# Mosfets.net
KiCad netlist of a schematic drawn in Altium Designer
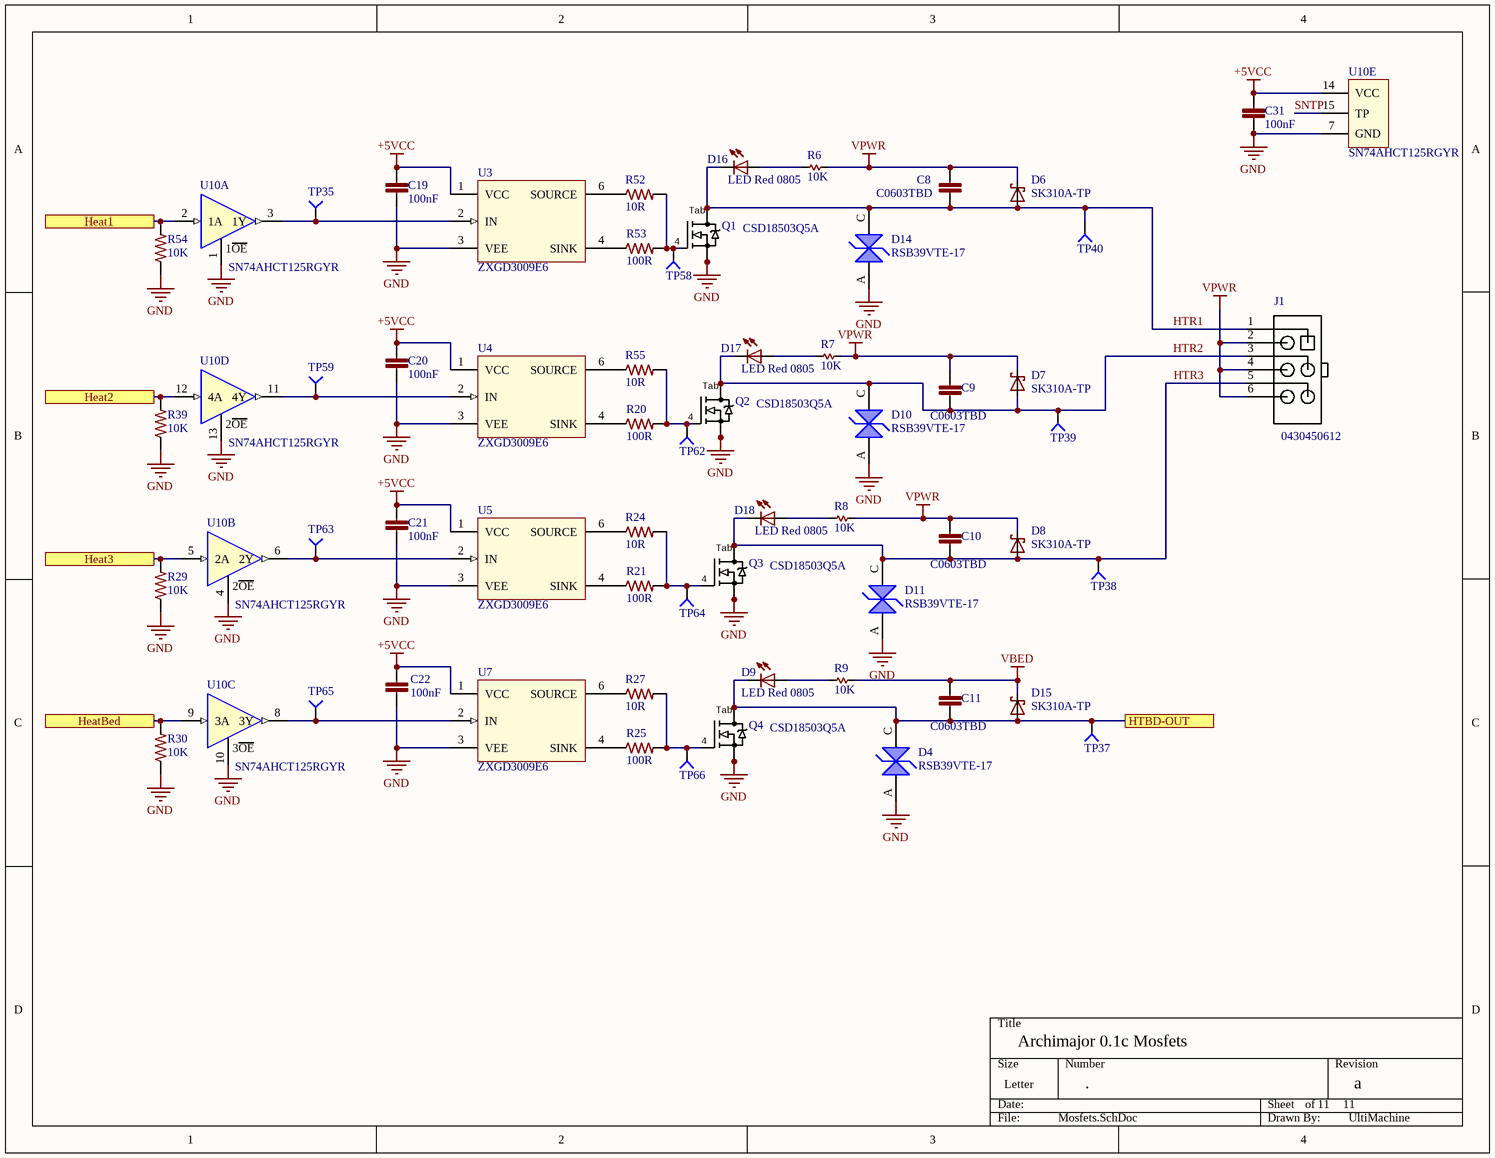
[diagram p0: Mosfets.SchDoc]

(export (version "E")
  (design (tool "Eeschema 10.0.6"))
  (components
    (comp (ref "C8")
      (value "C0603TBD")
      (footprint "C0603")
      (description "Capacitor Non Polarized")
      (libsource (lib "3Delight") (part "C0603TBD"))
    )
    (comp (ref "C9")
      (value "C0603TBD")
      (footprint "C0603")
      (description "Capacitor Non Polarized")
      (libsource (lib "3Delight") (part "C0603TBD"))
    )
    (comp (ref "C10")
      (value "C0603TBD")
      (footprint "C0603")
      (description "Capacitor Non Polarized")
      (libsource (lib "3Delight") (part "C0603TBD"))
    )
    (comp (ref "C11")
      (value "C0603TBD")
      (footprint "C0603")
      (description "Capacitor Non Polarized")
      (libsource (lib "3Delight") (part "C0603TBD"))
    )
    (comp (ref "C19")
      (value "100nF")
      (footprint "C0402")
      (description "CAP CER 0402 100nF 16V 10% X7R")
      (fields (field (name "MANUFACTURER") "Murata") (field (name "PART") "0.1uF 16V X7R 0402"))
      (libsource (lib "3Delight") (part "GRM155R71C104KA88D"))
    )
    (comp (ref "C20")
      (value "100nF")
      (footprint "C0402")
      (description "CAP CER 0402 100nF 16V 10% X7R")
      (fields (field (name "MANUFACTURER") "Murata") (field (name "PART") "0.1uF 16V X7R 0402"))
      (libsource (lib "3Delight") (part "GRM155R71C104KA88D"))
    )
    (comp (ref "C21")
      (value "100nF")
      (footprint "C0402")
      (description "CAP CER 0402 100nF 16V 10% X7R")
      (fields (field (name "MANUFACTURER") "Murata") (field (name "PART") "0.1uF 16V X7R 0402"))
      (libsource (lib "3Delight") (part "GRM155R71C104KA88D"))
    )
    (comp (ref "C22")
      (value "100nF")
      (footprint "C0402")
      (description "CAP CER 0402 100nF 16V 10% X7R")
      (fields (field (name "MANUFACTURER") "Murata") (field (name "PART") "0.1uF 16V X7R 0402"))
      (libsource (lib "") (part "GRM155R71C104KA88D_1"))
    )
    (comp (ref "C31")
      (value "100nF")
      (footprint "C0402")
      (description "CAP CER 0402 100nF 16V 10% X7R")
      (fields (field (name "MANUFACTURER") "Murata") (field (name "PART") "0.1uF 16V X7R 0402"))
      (libsource (lib "3Delight") (part "GRM155R71C104KA88D"))
    )
    (comp (ref "D4")
      (value "RSB39VTE-17")
      (footprint "SOD323-R")
      (description "DIODE TVS")
      (fields (field (name "MANUFACTURER") "Rohm") (field (name "PART") "TVS DIODE 30VWM SOD323"))
      (libsource (lib "3Delight") (part "RSB39VTE-17"))
    )
    (comp (ref "D6")
      (value "SK310A-TP")
      (footprint "SMA-SM")
      (description "DIODE Schottky 3A SMA")
      (fields (field (name "MANUFACTURER") "MCC") (field (name "PART") "Schottky Diode 100V 3A"))
      (libsource (lib "Archim_0.4") (part "SK310A"))
    )
    (comp (ref "D7")
      (value "SK310A-TP")
      (footprint "SMA-SM")
      (description "DIODE Schottky 3A SMA")
      (fields (field (name "MANUFACTURER") "MCC") (field (name "PART") "Schottky Diode 100V 3A"))
      (libsource (lib "Archim_0.4") (part "SK310A"))
    )
    (comp (ref "D8")
      (value "SK310A-TP")
      (footprint "SMA-SM")
      (description "DIODE Schottky 3A SMA")
      (fields (field (name "MANUFACTURER") "MCC") (field (name "PART") "Schottky Diode 100V 3A"))
      (libsource (lib "Archim_0.4") (part "SK310A"))
    )
    (comp (ref "D9")
      (value "Red")
      (footprint "LED2012120")
      (description "LED 0805 Red")
      (fields
        (field (name "MANUFACTURER") "Dialight")
        (field (name "PART") "LED Red 0805")
        (field (name "TOLERANCE") "-NA-")
      )
      (libsource (lib "3Delight") (part "5988110107F"))
    )
    (comp (ref "D10")
      (value "RSB39VTE-17")
      (footprint "SOD323-R")
      (description "DIODE TVS")
      (fields (field (name "MANUFACTURER") "Rohm") (field (name "PART") "TVS DIODE 30VWM SOD323"))
      (libsource (lib "3Delight") (part "RSB39VTE-17"))
    )
    (comp (ref "D11")
      (value "RSB39VTE-17")
      (footprint "SOD323-R")
      (description "DIODE TVS")
      (fields (field (name "MANUFACTURER") "Rohm") (field (name "PART") "TVS DIODE 30VWM SOD323"))
      (libsource (lib "3Delight") (part "RSB39VTE-17"))
    )
    (comp (ref "D14")
      (value "RSB39VTE-17")
      (footprint "SOD323-R")
      (description "DIODE TVS")
      (fields (field (name "MANUFACTURER") "Rohm") (field (name "PART") "TVS DIODE 30VWM SOD323"))
      (libsource (lib "3Delight") (part "RSB39VTE-17"))
    )
    (comp (ref "D15")
      (value "SK310A-TP")
      (footprint "SMA-SM")
      (description "DIODE Schottky 3A SMA")
      (fields (field (name "MANUFACTURER") "MCC") (field (name "PART") "Schottky Diode 100V 3A"))
      (libsource (lib "Archim_0.4") (part "SK310A"))
    )
    (comp (ref "D16")
      (value "Red")
      (footprint "LED2012120")
      (description "LED 0805 Red")
      (fields
        (field (name "MANUFACTURER") "Dialight")
        (field (name "PART") "LED Red 0805")
        (field (name "TOLERANCE") "-NA-")
      )
      (libsource (lib "3Delight") (part "5988110107F"))
    )
    (comp (ref "D17")
      (value "Red")
      (footprint "LED2012120")
      (description "LED 0805 Red")
      (fields
        (field (name "MANUFACTURER") "Dialight")
        (field (name "PART") "LED Red 0805")
        (field (name "TOLERANCE") "-NA-")
      )
      (libsource (lib "3Delight") (part "5988110107F"))
    )
    (comp (ref "D18")
      (value "Red")
      (footprint "LED2012120")
      (description "LED 0805 Red")
      (fields
        (field (name "MANUFACTURER") "Dialight")
        (field (name "PART") "LED Red 0805")
        (field (name "TOLERANCE") "-NA-")
      )
      (libsource (lib "3Delight") (part "5988110107F"))
    )
    (comp (ref "J1")
      (value "0430450612")
      (footprint "43045-0612")
      (description "Conn - 3mm Pitch Fixed")
      (fields (field (name "MANUFACTURER") "Molex"))
      (libsource (lib "Connectors") (part "Micro-Fit THT 6pos 3mm"))
    )
    (comp (ref "Q1")
      (value "CSD18503Q5A")
      (footprint "SOT669_Universal")
      (description "MOSFET N-CH 40V 100A 8VSON")
      (fields (field (name "MANUFACTURER") "TI"))
      (libsource (lib "Transistors") (part "CSD18503Q5A"))
    )
    (comp (ref "Q2")
      (value "CSD18503Q5A")
      (footprint "SOT669_Universal")
      (description "MOSFET N-CH 40V 100A 8VSON")
      (fields (field (name "MANUFACTURER") "TI"))
      (libsource (lib "Transistors") (part "CSD18503Q5A"))
    )
    (comp (ref "Q3")
      (value "CSD18503Q5A")
      (footprint "SOT669_Universal")
      (description "MOSFET N-CH 40V 100A 8VSON")
      (fields (field (name "MANUFACTURER") "TI"))
      (libsource (lib "Transistors") (part "CSD18503Q5A"))
    )
    (comp (ref "Q4")
      (value "CSD18503Q5A")
      (footprint "SOT669_Universal")
      (description "MOSFET N-CH 40V 100A 8VSON")
      (fields (field (name "MANUFACTURER") "TI"))
      (libsource (lib "Transistors") (part "CSD18503Q5A"))
    )
    (comp (ref "R6")
      (value "10K")
      (footprint "R0402")
      (description "RES SMD 10K OHM 1% 1/16W 0402")
      (fields (field (name "MANUFACTURER") "Yageo") (field (name "PART") "10k 1% 0402"))
      (libsource (lib "Resistors") (part "10k 1% 0402"))
    )
    (comp (ref "R7")
      (value "10K")
      (footprint "R0402")
      (description "RES SMD 10K OHM 1% 1/16W 0402")
      (fields (field (name "MANUFACTURER") "Yageo") (field (name "PART") "10k 1% 0402"))
      (libsource (lib "Resistors") (part "10k 1% 0402"))
    )
    (comp (ref "R8")
      (value "10K")
      (footprint "R0402")
      (description "RES SMD 10K OHM 1% 1/16W 0402")
      (fields (field (name "MANUFACTURER") "Yageo") (field (name "PART") "10k 1% 0402"))
      (libsource (lib "Resistors") (part "10k 1% 0402"))
    )
    (comp (ref "R9")
      (value "10K")
      (footprint "R0402")
      (description "RES SMD 10K OHM 1% 1/16W 0402")
      (fields (field (name "MANUFACTURER") "Yageo") (field (name "PART") "10k 1% 0402"))
      (libsource (lib "Resistors") (part "10k 1% 0402"))
    )
    (comp (ref "R20")
      (value "100R")
      (footprint "R0402")
      (description "RES SMD 100 OHM 1% 1/16W 0402")
      (fields (field (name "MANUFACTURER") "Yageo") (field (name "PART") "100R 1% 0402"))
      (libsource (lib "Archim") (part "RES 100R 0402 1%"))
    )
    (comp (ref "R21")
      (value "100R")
      (footprint "R0402")
      (description "RES SMD 100 OHM 1% 1/16W 0402")
      (fields (field (name "MANUFACTURER") "Yageo") (field (name "PART") "100R 1% 0402"))
      (libsource (lib "Archim") (part "RES 100R 0402 1%"))
    )
    (comp (ref "R24")
      (value "10R")
      (footprint "R0402")
      (description "RES SMD 10 OHM 1% 1/16W 0402")
      (fields (field (name "MANUFACTURER") "Yageo") (field (name "TOLERANCE") "1%"))
      (libsource (lib "3Delight") (part "RC0402FR-0710RL"))
    )
    (comp (ref "R25")
      (value "100R")
      (footprint "R0402")
      (description "RES SMD 100 OHM 1% 1/16W 0402")
      (fields (field (name "MANUFACTURER") "Yageo") (field (name "PART") "100R 1% 0402"))
      (libsource (lib "Archim") (part "RES 100R 0402 1%"))
    )
    (comp (ref "R27")
      (value "10R")
      (footprint "R0402")
      (description "RES SMD 10 OHM 1% 1/16W 0402")
      (fields (field (name "MANUFACTURER") "Yageo") (field (name "TOLERANCE") "1%"))
      (libsource (lib "3Delight") (part "RC0402FR-0710RL"))
    )
    (comp (ref "R29")
      (value "10K")
      (footprint "R0402")
      (description "RES SMD 10K OHM 1% 1/16W 0402")
      (fields (field (name "MANUFACTURER") "Yageo") (field (name "PART") "10k 1% 0402"))
      (libsource (lib "3Delight") (part "RC0402FR-0710KP"))
    )
    (comp (ref "R30")
      (value "10K")
      (footprint "R0402")
      (description "RES SMD 10K OHM 1% 1/16W 0402")
      (fields (field (name "MANUFACTURER") "Yageo") (field (name "PART") "10k 1% 0402"))
      (libsource (lib "3Delight") (part "RC0402FR-0710KP"))
    )
    (comp (ref "R39")
      (value "10K")
      (footprint "R0402")
      (description "RES SMD 10K OHM 1% 1/16W 0402")
      (fields (field (name "MANUFACTURER") "Yageo") (field (name "PART") "10k 1% 0402"))
      (libsource (lib "3Delight") (part "RC0402FR-0710KP"))
    )
    (comp (ref "R52")
      (value "10R")
      (footprint "R0402")
      (description "RES SMD 10 OHM 1% 1/16W 0402")
      (fields (field (name "MANUFACTURER") "Yageo") (field (name "TOLERANCE") "1%"))
      (libsource (lib "3Delight") (part "RC0402FR-0710RL"))
    )
    (comp (ref "R53")
      (value "100R")
      (footprint "R0402")
      (description "RES SMD 100 OHM 1% 1/16W 0402")
      (fields (field (name "MANUFACTURER") "Yageo") (field (name "PART") "100R 1% 0402"))
      (libsource (lib "Archim") (part "RES 100R 0402 1%"))
    )
    (comp (ref "R54")
      (value "10K")
      (footprint "R0402")
      (description "RES SMD 10K OHM 1% 1/16W 0402")
      (fields (field (name "MANUFACTURER") "Yageo") (field (name "PART") "10k 1% 0402"))
      (libsource (lib "3Delight") (part "RC0402FR-0710KP"))
    )
    (comp (ref "R55")
      (value "10R")
      (footprint "R0402")
      (description "RES SMD 10 OHM 1% 1/16W 0402")
      (fields (field (name "MANUFACTURER") "Yageo") (field (name "TOLERANCE") "1%"))
      (libsource (lib "3Delight") (part "RC0402FR-0710RL"))
    )
    (comp (ref "TP35")
      (value "TP4")
      (footprint "TP-2")
      (description "Socket")
      (libsource (lib "Archim") (part "Socket"))
    )
    (comp (ref "TP37")
      (value "TP4")
      (footprint "TP-2")
      (description "Socket")
      (libsource (lib "Archim") (part "Socket"))
    )
    (comp (ref "TP38")
      (value "TP4")
      (footprint "TP-2")
      (description "Socket")
      (libsource (lib "Archim") (part "Socket"))
    )
    (comp (ref "TP39")
      (value "TP4")
      (footprint "TP-2")
      (description "Socket")
      (libsource (lib "Archim") (part "Socket"))
    )
    (comp (ref "TP40")
      (value "TP4")
      (footprint "TP-2")
      (description "Socket")
      (libsource (lib "Archim") (part "Socket"))
    )
    (comp (ref "TP58")
      (value "TP4")
      (footprint "TP-2")
      (description "Socket")
      (libsource (lib "Archim") (part "Socket"))
    )
    (comp (ref "TP59")
      (value "TP4")
      (footprint "TP-2")
      (description "Socket")
      (libsource (lib "Archim") (part "Socket"))
    )
    (comp (ref "TP62")
      (value "TP4")
      (footprint "TP-2")
      (description "Socket")
      (libsource (lib "Archim") (part "Socket"))
    )
    (comp (ref "TP63")
      (value "TP4")
      (footprint "TP-2")
      (description "Socket")
      (libsource (lib "Archim") (part "Socket"))
    )
    (comp (ref "TP64")
      (value "TP4")
      (footprint "TP-2")
      (description "Socket")
      (libsource (lib "Archim") (part "Socket"))
    )
    (comp (ref "TP65")
      (value "TP4")
      (footprint "TP-2")
      (description "Socket")
      (libsource (lib "Archim") (part "Socket"))
    )
    (comp (ref "TP66")
      (value "TP4")
      (footprint "TP-2")
      (description "Socket")
      (libsource (lib "Archim") (part "Socket"))
    )
    (comp (ref "U3")
      (value "ZXGD3009E6")
      (footprint "SOT26P285X140-6L")
      (description "MOSFET DRVR 3A 1-OUT High Speed Non-Inv6-Pin SOT-26 T/R")
      (fields
        (field (name "MANUFACTURER") "Diodes Incorporated")
        (field (name "PART") "IC GATE DRVR IGBT/MOSFET SOT23-6")
      )
      (libsource (lib "3Delight") (part "ZXGD3009E6"))
    )
    (comp (ref "U4")
      (value "ZXGD3009E6")
      (footprint "SOT26P285X140-6L")
      (description "MOSFET DRVR 3A 1-OUT High Speed Non-Inv6-Pin SOT-26 T/R")
      (fields
        (field (name "MANUFACTURER") "Diodes Incorporated")
        (field (name "PART") "IC GATE DRVR IGBT/MOSFET SOT23-6")
      )
      (libsource (lib "3Delight") (part "ZXGD3009E6"))
    )
    (comp (ref "U5")
      (value "ZXGD3009E6")
      (footprint "SOT26P285X140-6L")
      (description "MOSFET DRVR 3A 1-OUT High Speed Non-Inv6-Pin SOT-26 T/R")
      (fields
        (field (name "MANUFACTURER") "Diodes Incorporated")
        (field (name "PART") "IC GATE DRVR IGBT/MOSFET SOT23-6")
      )
      (libsource (lib "3Delight") (part "ZXGD3009E6"))
    )
    (comp (ref "U7")
      (value "ZXGD3009E6")
      (footprint "SOT26P285X140-6L")
      (description "MOSFET DRVR 3A 1-OUT High Speed Non-Inv6-Pin SOT-26 T/R")
      (fields
        (field (name "MANUFACTURER") "Diodes Incorporated")
        (field (name "PART") "IC GATE DRVR IGBT/MOSFET SOT23-6")
      )
      (libsource (lib "3Delight") (part "ZXGD3009E6"))
    )
    (comp (ref "U10")
      (value "SN74AHCT125RGYR")
      (footprint "QFN50P350X350X100_RGY_S-PVQFN-N14")
      (description "Quadruple Bus Buffer Gates With 3-State Outputs 14-VQFN -40 to 125")
      (fields
        (field (name "MANUFACTURER") "Texas Instruments")
        (field (name "PART") "IC BUS BUFFER TRI-ST QD 14VQFN")
      )
      (libsource (lib "3Delight") (part "SN74AHCT125"))
    )
  )
  (nets
    (net (code "1") (name "+5VCC") (class "Default")
      (node (ref "C19") (pin "2") (pinfunction "2_2") (pintype "passive"))
      (node (ref "C20") (pin "2") (pinfunction "2_2") (pintype "passive"))
      (node (ref "C21") (pin "2") (pinfunction "2_2") (pintype "passive"))
      (node (ref "C22") (pin "1") (pinfunction "1_1") (pintype "passive"))
      (node (ref "C31") (pin "2") (pinfunction "2_2") (pintype "passive"))
      (node (ref "U10") (pin "14") (pinfunction "VCC_14") (pintype "power_in"))
      (node (ref "U3") (pin "1") (pinfunction "VCC_1") (pintype "power_in"))
      (node (ref "U4") (pin "1") (pinfunction "VCC_1") (pintype "power_in"))
      (node (ref "U5") (pin "1") (pinfunction "VCC_1") (pintype "power_in"))
      (node (ref "U7") (pin "1") (pinfunction "VCC_1") (pintype "power_in"))
    )
    (net (code "2") (name "/HTBD-OUT") (class "Default")
      (node (ref "C11") (pin "2") (pinfunction "2_2") (pintype "passive"))
      (node (ref "D15") (pin "A") (pinfunction "A_A") (pintype "passive"))
      (node (ref "D4") (pin "C") (pinfunction "C_C") (pintype "power_in"))
      (node (ref "D9") (pin "C") (pinfunction "C_C") (pintype "passive"))
      (node (ref "Q4") (pin "TAB") (pinfunction "D_TAB") (pintype "passive"))
      (node (ref "TP37") (pin "1") (pinfunction "1_1") (pintype "passive"))
    )
    (net (code "3") (name "/HTR1") (class "Default")
      (node (ref "C8") (pin "2") (pinfunction "2_2") (pintype "passive"))
      (node (ref "D14") (pin "C") (pinfunction "C_C") (pintype "power_in"))
      (node (ref "D16") (pin "C") (pinfunction "C_C") (pintype "passive"))
      (node (ref "D6") (pin "A") (pinfunction "A_A") (pintype "passive"))
      (node (ref "J1") (pin "1") (pinfunction "1_1") (pintype "power_in"))
      (node (ref "Q1") (pin "TAB") (pinfunction "D_TAB") (pintype "passive"))
      (node (ref "TP40") (pin "1") (pinfunction "1_1") (pintype "passive"))
    )
    (net (code "4") (name "/HTR2") (class "Default")
      (node (ref "C9") (pin "2") (pinfunction "2_2") (pintype "passive"))
      (node (ref "D10") (pin "C") (pinfunction "C_C") (pintype "power_in"))
      (node (ref "D17") (pin "C") (pinfunction "C_C") (pintype "passive"))
      (node (ref "D7") (pin "A") (pinfunction "A_A") (pintype "passive"))
      (node (ref "J1") (pin "3") (pinfunction "3_3") (pintype "power_in"))
      (node (ref "Q2") (pin "TAB") (pinfunction "D_TAB") (pintype "passive"))
      (node (ref "TP39") (pin "1") (pinfunction "1_1") (pintype "passive"))
    )
    (net (code "5") (name "/HTR3") (class "Default")
      (node (ref "C10") (pin "2") (pinfunction "2_2") (pintype "passive"))
      (node (ref "D11") (pin "C") (pinfunction "C_C") (pintype "power_in"))
      (node (ref "D18") (pin "C") (pinfunction "C_C") (pintype "passive"))
      (node (ref "D8") (pin "A") (pinfunction "A_A") (pintype "passive"))
      (node (ref "J1") (pin "5") (pinfunction "5_5") (pintype "power_in"))
      (node (ref "Q3") (pin "TAB") (pinfunction "D_TAB") (pintype "passive"))
      (node (ref "TP38") (pin "1") (pinfunction "1_1") (pintype "passive"))
    )
    (net (code "6") (name "/Heat1") (class "Default")
      (node (ref "R54") (pin "2") (pinfunction "2_2") (pintype "passive"))
      (node (ref "U10") (pin "2") (pinfunction "1A_2") (pintype "input"))
    )
    (net (code "7") (name "/Heat2") (class "Default")
      (node (ref "R39") (pin "2") (pinfunction "2_2") (pintype "passive"))
      (node (ref "U10") (pin "12") (pinfunction "4A_12") (pintype "input"))
    )
    (net (code "8") (name "/Heat3") (class "Default")
      (node (ref "R29") (pin "2") (pinfunction "2_2") (pintype "passive"))
      (node (ref "U10") (pin "5") (pinfunction "2A_5") (pintype "input"))
    )
    (net (code "9") (name "/HeatBed") (class "Default")
      (node (ref "R30") (pin "2") (pinfunction "2_2") (pintype "passive"))
      (node (ref "U10") (pin "9") (pinfunction "3A_9") (pintype "input"))
    )
    (net (code "10") (name "/SNTP") (class "Default")
      (node (ref "U10") (pin "15") (pinfunction "TP_15") (pintype "power_in"))
    )
    (net (code "11") (name "GND") (class "Default")
      (node (ref "C19") (pin "1") (pinfunction "1_1") (pintype "passive"))
      (node (ref "C20") (pin "1") (pinfunction "1_1") (pintype "passive"))
      (node (ref "C21") (pin "1") (pinfunction "1_1") (pintype "passive"))
      (node (ref "C22") (pin "2") (pinfunction "2_2") (pintype "passive"))
      (node (ref "C31") (pin "1") (pinfunction "1_1") (pintype "passive"))
      (node (ref "D10") (pin "A") (pinfunction "A_A") (pintype "power_in"))
      (node (ref "D11") (pin "A") (pinfunction "A_A") (pintype "power_in"))
      (node (ref "D14") (pin "A") (pinfunction "A_A") (pintype "power_in"))
      (node (ref "D4") (pin "A") (pinfunction "A_A") (pintype "power_in"))
      (node (ref "Q1") (pin "1") (pinfunction "S_1") (pintype "passive"))
      (node (ref "Q1") (pin "2") (pinfunction "S_2") (pintype "passive"))
      (node (ref "Q1") (pin "3") (pinfunction "S_3") (pintype "passive"))
      (node (ref "Q2") (pin "1") (pinfunction "S_1") (pintype "passive"))
      (node (ref "Q2") (pin "2") (pinfunction "S_2") (pintype "passive"))
      (node (ref "Q2") (pin "3") (pinfunction "S_3") (pintype "passive"))
      (node (ref "Q3") (pin "1") (pinfunction "S_1") (pintype "passive"))
      (node (ref "Q3") (pin "2") (pinfunction "S_2") (pintype "passive"))
      (node (ref "Q3") (pin "3") (pinfunction "S_3") (pintype "passive"))
      (node (ref "Q4") (pin "1") (pinfunction "S_1") (pintype "passive"))
      (node (ref "Q4") (pin "2") (pinfunction "S_2") (pintype "passive"))
      (node (ref "Q4") (pin "3") (pinfunction "S_3") (pintype "passive"))
      (node (ref "R29") (pin "1") (pinfunction "1_1") (pintype "passive"))
      (node (ref "R30") (pin "1") (pinfunction "1_1") (pintype "passive"))
      (node (ref "R39") (pin "1") (pinfunction "1_1") (pintype "passive"))
      (node (ref "R54") (pin "1") (pinfunction "1_1") (pintype "passive"))
      (node (ref "U10") (pin "1") (pinfunction "1OE_1") (pintype "power_in"))
      (node (ref "U10") (pin "10") (pinfunction "3OE_10") (pintype "power_in"))
      (node (ref "U10") (pin "13") (pinfunction "4OE_13") (pintype "power_in"))
      (node (ref "U10") (pin "4") (pinfunction "2OE_4") (pintype "power_in"))
      (node (ref "U10") (pin "7") (pinfunction "GND_7") (pintype "power_in"))
      (node (ref "U3") (pin "3") (pinfunction "VEE_3") (pintype "power_in"))
      (node (ref "U4") (pin "3") (pinfunction "VEE_3") (pintype "power_in"))
      (node (ref "U5") (pin "3") (pinfunction "VEE_3") (pintype "power_in"))
      (node (ref "U7") (pin "3") (pinfunction "VEE_3") (pintype "power_in"))
    )
    (net (code "12") (name "Net-(D9-PadA)") (class "Default")
      (node (ref "D9") (pin "A") (pinfunction "A_A") (pintype "passive"))
      (node (ref "R9") (pin "1") (pinfunction "1_1") (pintype "passive"))
    )
    (net (code "13") (name "Net-(D16-PadA)") (class "Default")
      (node (ref "D16") (pin "A") (pinfunction "A_A") (pintype "passive"))
      (node (ref "R6") (pin "1") (pinfunction "1_1") (pintype "passive"))
    )
    (net (code "14") (name "Net-(D17-PadA)") (class "Default")
      (node (ref "D17") (pin "A") (pinfunction "A_A") (pintype "passive"))
      (node (ref "R7") (pin "1") (pinfunction "1_1") (pintype "passive"))
    )
    (net (code "15") (name "Net-(D18-PadA)") (class "Default")
      (node (ref "D18") (pin "A") (pinfunction "A_A") (pintype "passive"))
      (node (ref "R8") (pin "1") (pinfunction "1_1") (pintype "passive"))
    )
    (net (code "16") (name "Net-(Q1-G)") (class "Default")
      (node (ref "Q1") (pin "4") (pinfunction "G_4") (pintype "passive"))
      (node (ref "R52") (pin "2") (pinfunction "2_2") (pintype "passive"))
      (node (ref "R53") (pin "2") (pinfunction "2_2") (pintype "passive"))
      (node (ref "TP58") (pin "1") (pinfunction "1_1") (pintype "passive"))
    )
    (net (code "17") (name "Net-(Q2-G)") (class "Default")
      (node (ref "Q2") (pin "4") (pinfunction "G_4") (pintype "passive"))
      (node (ref "R20") (pin "2") (pinfunction "2_2") (pintype "passive"))
      (node (ref "R55") (pin "2") (pinfunction "2_2") (pintype "passive"))
      (node (ref "TP62") (pin "1") (pinfunction "1_1") (pintype "passive"))
    )
    (net (code "18") (name "Net-(Q3-G)") (class "Default")
      (node (ref "Q3") (pin "4") (pinfunction "G_4") (pintype "passive"))
      (node (ref "R21") (pin "2") (pinfunction "2_2") (pintype "passive"))
      (node (ref "R24") (pin "2") (pinfunction "2_2") (pintype "passive"))
      (node (ref "TP64") (pin "1") (pinfunction "1_1") (pintype "passive"))
    )
    (net (code "19") (name "Net-(Q4-G)") (class "Default")
      (node (ref "Q4") (pin "4") (pinfunction "G_4") (pintype "passive"))
      (node (ref "R25") (pin "2") (pinfunction "2_2") (pintype "passive"))
      (node (ref "R27") (pin "2") (pinfunction "2_2") (pintype "passive"))
      (node (ref "TP66") (pin "1") (pinfunction "1_1") (pintype "passive"))
    )
    (net (code "20") (name "Net-(U3-SINK)") (class "Default")
      (node (ref "R53") (pin "1") (pinfunction "1_1") (pintype "passive"))
      (node (ref "U3") (pin "4") (pinfunction "SINK_4") (pintype "power_in"))
    )
    (net (code "21") (name "Net-(U3-SOURCE)") (class "Default")
      (node (ref "R52") (pin "1") (pinfunction "1_1") (pintype "passive"))
      (node (ref "U3") (pin "6") (pinfunction "SOURCE_6") (pintype "power_in"))
    )
    (net (code "22") (name "Net-(U4-SINK)") (class "Default")
      (node (ref "R20") (pin "1") (pinfunction "1_1") (pintype "passive"))
      (node (ref "U4") (pin "4") (pinfunction "SINK_4") (pintype "power_in"))
    )
    (net (code "23") (name "Net-(U4-SOURCE)") (class "Default")
      (node (ref "R55") (pin "1") (pinfunction "1_1") (pintype "passive"))
      (node (ref "U4") (pin "6") (pinfunction "SOURCE_6") (pintype "power_in"))
    )
    (net (code "24") (name "Net-(U5-SINK)") (class "Default")
      (node (ref "R21") (pin "1") (pinfunction "1_1") (pintype "passive"))
      (node (ref "U5") (pin "4") (pinfunction "SINK_4") (pintype "power_in"))
    )
    (net (code "25") (name "Net-(U5-SOURCE)") (class "Default")
      (node (ref "R24") (pin "1") (pinfunction "1_1") (pintype "passive"))
      (node (ref "U5") (pin "6") (pinfunction "SOURCE_6") (pintype "power_in"))
    )
    (net (code "26") (name "Net-(U7-SINK)") (class "Default")
      (node (ref "R25") (pin "1") (pinfunction "1_1") (pintype "passive"))
      (node (ref "U7") (pin "4") (pinfunction "SINK_4") (pintype "power_in"))
    )
    (net (code "27") (name "Net-(U7-SOURCE)") (class "Default")
      (node (ref "R27") (pin "1") (pinfunction "1_1") (pintype "passive"))
      (node (ref "U7") (pin "6") (pinfunction "SOURCE_6") (pintype "power_in"))
    )
    (net (code "28") (name "Net-(U10A-1Y)") (class "Default")
      (node (ref "TP35") (pin "1") (pinfunction "1_1") (pintype "passive"))
      (node (ref "U10") (pin "3") (pinfunction "1Y_3") (pintype "output"))
      (node (ref "U3") (pin "2") (pinfunction "IN_2") (pintype "input"))
    )
    (net (code "29") (name "Net-(U10B-2Y)") (class "Default")
      (node (ref "TP63") (pin "1") (pinfunction "1_1") (pintype "passive"))
      (node (ref "U10") (pin "6") (pinfunction "2Y_6") (pintype "output"))
      (node (ref "U5") (pin "2") (pinfunction "IN_2") (pintype "input"))
    )
    (net (code "30") (name "Net-(U10C-3Y)") (class "Default")
      (node (ref "TP65") (pin "1") (pinfunction "1_1") (pintype "passive"))
      (node (ref "U10") (pin "8") (pinfunction "3Y_8") (pintype "output"))
      (node (ref "U7") (pin "2") (pinfunction "IN_2") (pintype "input"))
    )
    (net (code "31") (name "Net-(U10D-4Y)") (class "Default")
      (node (ref "TP59") (pin "1") (pinfunction "1_1") (pintype "passive"))
      (node (ref "U10") (pin "11") (pinfunction "4Y_11") (pintype "output"))
      (node (ref "U4") (pin "2") (pinfunction "IN_2") (pintype "input"))
    )
    (net (code "32") (name "VBED") (class "Default")
      (node (ref "C11") (pin "1") (pinfunction "1_1") (pintype "passive"))
      (node (ref "D15") (pin "C") (pinfunction "C_C") (pintype "passive"))
      (node (ref "R9") (pin "2") (pinfunction "2_2") (pintype "passive"))
    )
    (net (code "33") (name "VPWR") (class "Default")
      (node (ref "C10") (pin "1") (pinfunction "1_1") (pintype "passive"))
      (node (ref "C8") (pin "1") (pinfunction "1_1") (pintype "passive"))
      (node (ref "C9") (pin "1") (pinfunction "1_1") (pintype "passive"))
      (node (ref "D6") (pin "C") (pinfunction "C_C") (pintype "passive"))
      (node (ref "D7") (pin "C") (pinfunction "C_C") (pintype "passive"))
      (node (ref "D8") (pin "C") (pinfunction "C_C") (pintype "passive"))
      (node (ref "J1") (pin "2") (pinfunction "2_2") (pintype "power_in"))
      (node (ref "J1") (pin "4") (pinfunction "4_4") (pintype "power_in"))
      (node (ref "J1") (pin "6") (pinfunction "6_6") (pintype "power_in"))
      (node (ref "R6") (pin "2") (pinfunction "2_2") (pintype "passive"))
      (node (ref "R7") (pin "2") (pinfunction "2_2") (pintype "passive"))
      (node (ref "R8") (pin "2") (pinfunction "2_2") (pintype "passive"))
    )
  )
)
